# Sensor.net
KiCad netlist of a schematic drawn in Altium Designer
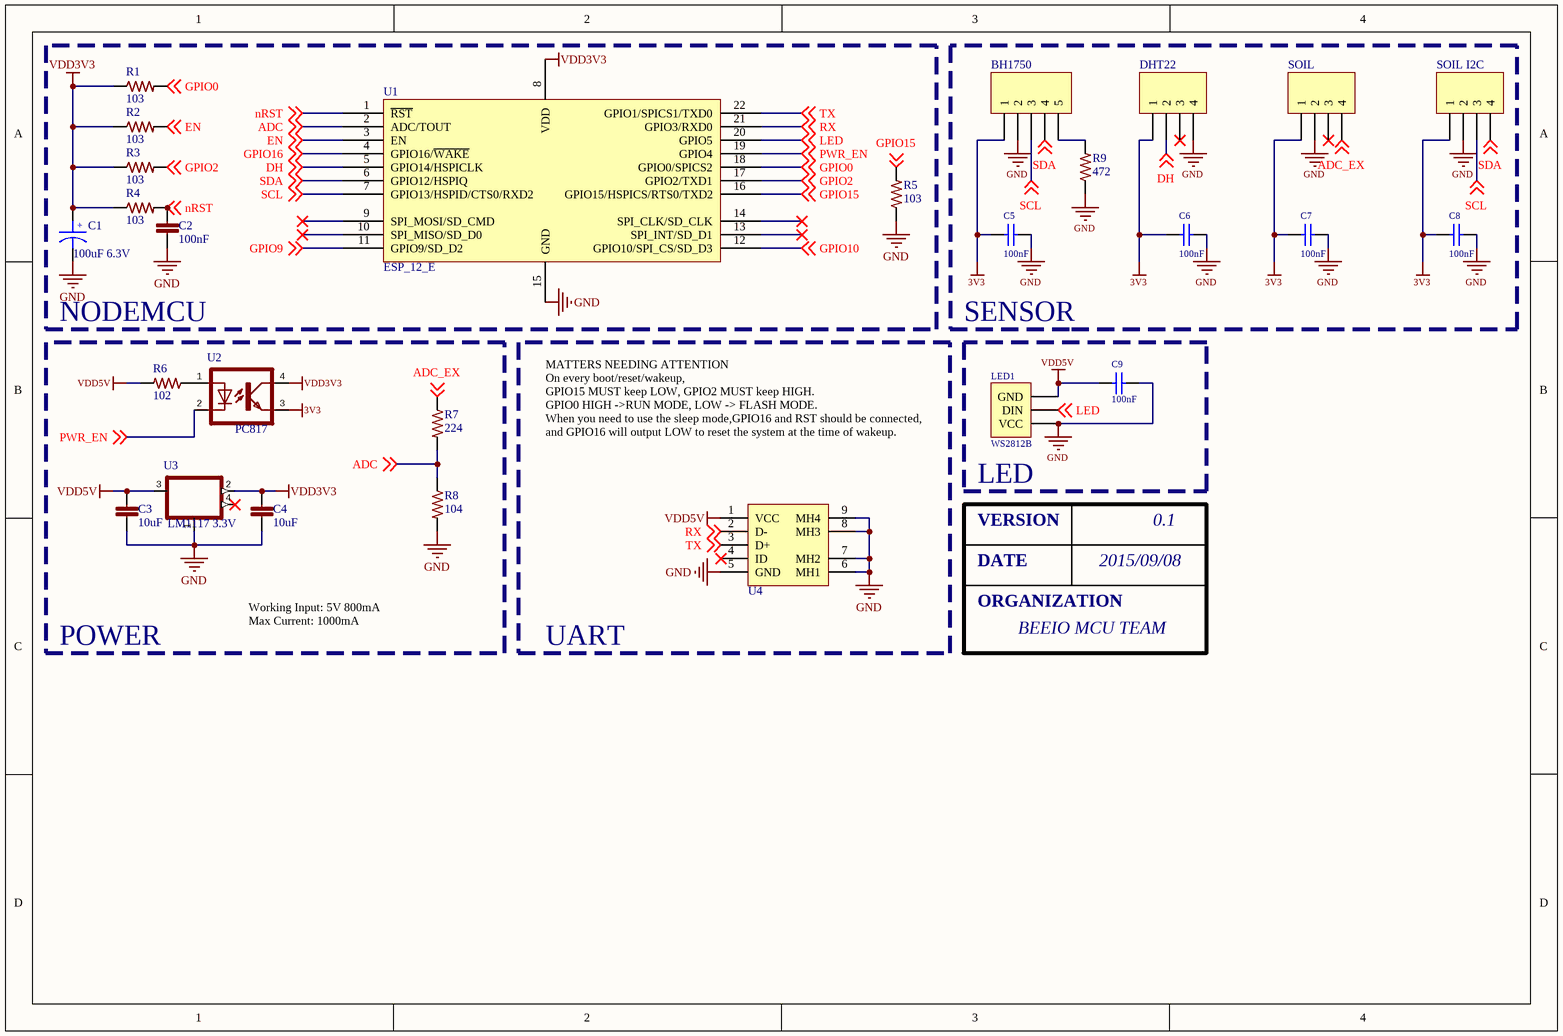
[diagram p0: Sensor.SchDoc]

(export (version "E")
  (design (tool "Eeschema 10.0.6"))
  (components
    (comp (ref "BH1750")
      (value "BH1750")
      (footprint "HDR1X5")
      (description "Header, 5-Pin")
      (fields (field (name "PUBLISHER") "Altium Limited"))
      (libsource (lib "Miscellaneous Connectors") (part "Header 5"))
    )
    (comp (ref "C1")
      (value "100uF 6.3V")
      (footprint "SMT_C_Tantalum_B")
      (description "Capacitor, SM Tantalum; Body 3.5 x 2.8 mm (LxW typ)")
      (libsource (lib "NODEMCU_DEVKIT_V1.0") (part "SMT_C_Tantalum_B"))
    )
    (comp (ref "C2") (value "100nF") (footprint "0603") (libsource (lib "") (part "CAP0603_1")))
    (comp (ref "C3") (value "10uF") (footprint "0603") (libsource (lib "SparkFun") (part "CAP0603")))
    (comp (ref "C4") (value "10uF") (footprint "0603") (libsource (lib "SparkFun") (part "CAP0603")))
    (comp (ref "C5")
      (value "100nF")
      (footprint "1608[0603]")
      (description "Capacitor (Semiconductor SIM Model)")
      (fields (field (name "PUBLISHER") "Altium Limited"))
      (libsource (lib "Miscellaneous Devices") (part "Cap Semi"))
    )
    (comp (ref "C6")
      (value "100nF")
      (footprint "1608[0603]")
      (description "Capacitor (Semiconductor SIM Model)")
      (fields (field (name "PUBLISHER") "Altium Limited"))
      (libsource (lib "Miscellaneous Devices") (part "Cap Semi"))
    )
    (comp (ref "C7")
      (value "100nF")
      (footprint "1608[0603]")
      (description "Capacitor (Semiconductor SIM Model)")
      (fields (field (name "PUBLISHER") "Altium Limited"))
      (libsource (lib "Miscellaneous Devices") (part "Cap Semi"))
    )
    (comp (ref "C8")
      (value "100nF")
      (footprint "1608[0603]")
      (description "Capacitor (Semiconductor SIM Model)")
      (fields (field (name "PUBLISHER") "Altium Limited"))
      (libsource (lib "Miscellaneous Devices") (part "Cap Semi"))
    )
    (comp (ref "C9")
      (value "100nF")
      (footprint "1608[0603]")
      (description "Capacitor (Semiconductor SIM Model)")
      (fields (field (name "PUBLISHER") "Altium Limited"))
      (libsource (lib "Miscellaneous Devices") (part "Cap Semi"))
    )
    (comp (ref "DHT22")
      (value "~")
      (footprint "HDR1X4")
      (description "Header, 4-Pin")
      (fields (field (name "PUBLISHER") "Altium Limited"))
      (libsource (lib "Miscellaneous Connectors") (part "Header 4"))
    )
    (comp (ref "LED1")
      (value "WS2812B")
      (footprint "HDR1X3")
      (description "Header, 3-Pin")
      (fields (field (name "PUBLISHER") "Altium Limited"))
      (libsource (lib "Miscellaneous Connectors") (part "Header 3"))
    )
    (comp (ref "R1") (value "103") (footprint "0603") (libsource (lib "SparkFun") (part "RESISTOR0603")))
    (comp (ref "R2") (value "103") (footprint "0603") (libsource (lib "SparkFun") (part "RESISTOR0603")))
    (comp (ref "R3") (value "103") (footprint "0603") (libsource (lib "SparkFun") (part "RESISTOR0603")))
    (comp (ref "R4") (value "103") (footprint "0603") (libsource (lib "SparkFun") (part "RESISTOR0603")))
    (comp (ref "R5") (value "103") (footprint "0603") (libsource (lib "SparkFun") (part "RESISTOR0603")))
    (comp (ref "R6") (value "102") (footprint "0603") (libsource (lib "SparkFun") (part "RESISTOR0603")))
    (comp (ref "R7") (value "224") (footprint "0603") (libsource (lib "SparkFun") (part "RESISTOR0603")))
    (comp (ref "R8") (value "104") (footprint "0603") (libsource (lib "SparkFun") (part "RESISTOR0603")))
    (comp (ref "R9") (value "472") (footprint "0603") (libsource (lib "SparkFun") (part "RESISTOR0603")))
    (comp (ref "SOIL")
      (value "~")
      (footprint "HDR1X4")
      (description "Header, 4-Pin")
      (fields (field (name "PUBLISHER") "Altium Limited"))
      (libsource (lib "Miscellaneous Connectors") (part "Header 4"))
    )
    (comp (ref "SOIL I2C")
      (value "BH1750")
      (footprint "HDR1X4")
      (description "Header, 4-Pin")
      (fields (field (name "PUBLISHER") "Altium Limited"))
      (libsource (lib "Miscellaneous Connectors") (part "Header 4"))
    )
    (comp (ref "U1")
      (value "ESP_12_E")
      (footprint "ESP_12_E_L")
      (description "ESP-12 Wi-Fi Module by AI-Thinker")
      (libsource (lib "NODEMCU_DEVKIT_V1.0") (part "ESP_12_E"))
    )
    (comp (ref "U2")
      (value "PC817")
      (footprint "DIL4-SMD")
      (fields (field (name "MPN") "PC817X4J000F"))
      (libsource (lib "optocoupler") (part "PC817"))
    )
    (comp (ref "U3")
      (value "LM1117 3.3V")
      (footprint "SOT223")
      (libsource (lib "SparkFun-PowerIC") (part "V_REG_LM1117SOT223"))
    )
    (comp (ref "U4")
      (value "Micro USB 5S DIP")
      (footprint "USB_MICRO_5S_B")
      (description "USB micro female SMT with 4 fixed foot")
      (libsource (lib "NODEMCU_DEVKIT_V1.0") (part "USB_Micro_5S_B"))
    )
  )
  (nets
    (net (code "1") (name "3V3") (class "Default")
      (node (ref "BH1750") (pin "1") (pinfunction "1_1") (pintype "passive"))
      (node (ref "C5") (pin "1") (pinfunction "1_1") (pintype "passive"))
      (node (ref "C6") (pin "1") (pinfunction "1_1") (pintype "passive"))
      (node (ref "C7") (pin "1") (pinfunction "1_1") (pintype "passive"))
      (node (ref "C8") (pin "1") (pinfunction "1_1") (pintype "passive"))
      (node (ref "DHT22") (pin "1") (pinfunction "1_1") (pintype "passive"))
      (node (ref "SOIL") (pin "1") (pinfunction "1_1") (pintype "passive"))
      (node (ref "SOIL I2C") (pin "1") (pinfunction "1_1") (pintype "passive"))
      (node (ref "U2") (pin "3") (pinfunction "EMIT_3") (pintype "passive"))
    )
    (net (code "2") (name "ADC") (class "Default")
      (node (ref "R7") (pin "2") (pinfunction "2_2") (pintype "passive"))
      (node (ref "R8") (pin "1") (pinfunction "1_1") (pintype "passive"))
      (node (ref "U1") (pin "2") (pinfunction "ADC/TOUT_2") (pintype "passive"))
    )
    (net (code "3") (name "ADC_EX") (class "Default")
      (node (ref "R7") (pin "1") (pinfunction "1_1") (pintype "passive"))
      (node (ref "SOIL") (pin "4") (pinfunction "4_4") (pintype "passive"))
    )
    (net (code "4") (name "DH") (class "Default")
      (node (ref "DHT22") (pin "2") (pinfunction "2_2") (pintype "passive"))
      (node (ref "U1") (pin "5") (pinfunction "GPIO14/HSPICLK_5") (pintype "passive"))
    )
    (net (code "5") (name "EN") (class "Default")
      (node (ref "R2") (pin "2") (pinfunction "2_2") (pintype "passive"))
      (node (ref "U1") (pin "3") (pinfunction "EN_3") (pintype "passive"))
    )
    (net (code "6") (name "GND") (class "Default")
      (node (ref "BH1750") (pin "2") (pinfunction "2_2") (pintype "passive"))
      (node (ref "C1") (pin "2") (pinfunction "2_2") (pintype "passive"))
      (node (ref "C2") (pin "2") (pinfunction "2_2") (pintype "passive"))
      (node (ref "C3") (pin "1") (pinfunction "1_1") (pintype "passive"))
      (node (ref "C4") (pin "1") (pinfunction "1_1") (pintype "passive"))
      (node (ref "C5") (pin "2") (pinfunction "2_2") (pintype "passive"))
      (node (ref "C6") (pin "2") (pinfunction "2_2") (pintype "passive"))
      (node (ref "C7") (pin "2") (pinfunction "2_2") (pintype "passive"))
      (node (ref "C8") (pin "2") (pinfunction "2_2") (pintype "passive"))
      (node (ref "C9") (pin "2") (pinfunction "2_2") (pintype "passive"))
      (node (ref "DHT22") (pin "4") (pinfunction "4_4") (pintype "passive"))
      (node (ref "LED1") (pin "1") (pinfunction "VCC_1") (pintype "passive"))
      (node (ref "R5") (pin "1") (pinfunction "1_1") (pintype "passive"))
      (node (ref "R8") (pin "2") (pinfunction "2_2") (pintype "passive"))
      (node (ref "R9") (pin "1") (pinfunction "1_1") (pintype "passive"))
      (node (ref "SOIL") (pin "2") (pinfunction "2_2") (pintype "passive"))
      (node (ref "SOIL I2C") (pin "2") (pinfunction "2_2") (pintype "passive"))
      (node (ref "U1") (pin "15") (pinfunction "GND_15") (pintype "passive"))
      (node (ref "U3") (pin "1") (pinfunction "ADJ_1") (pintype "passive"))
      (node (ref "U4") (pin "5") (pinfunction "GND_5") (pintype "passive"))
      (node (ref "U4") (pin "6") (pinfunction "MH1_6") (pintype "passive"))
      (node (ref "U4") (pin "7") (pinfunction "MH2_7") (pintype "passive"))
      (node (ref "U4") (pin "8") (pinfunction "MH3_8") (pintype "passive"))
      (node (ref "U4") (pin "9") (pinfunction "MH4_9") (pintype "passive"))
    )
    (net (code "7") (name "GPIO0") (class "Default")
      (node (ref "R1") (pin "2") (pinfunction "2_2") (pintype "passive"))
      (node (ref "U1") (pin "18") (pinfunction "GPIO0/SPICS2_18") (pintype "passive"))
    )
    (net (code "8") (name "GPIO2") (class "Default")
      (node (ref "R3") (pin "2") (pinfunction "2_2") (pintype "passive"))
      (node (ref "U1") (pin "17") (pinfunction "GPIO2/TXD1_17") (pintype "passive"))
    )
    (net (code "9") (name "GPIO9") (class "Default")
      (node (ref "U1") (pin "11") (pinfunction "GPIO9/SD_D2_11") (pintype "passive"))
    )
    (net (code "10") (name "GPIO10") (class "Default")
      (node (ref "U1") (pin "12") (pinfunction "GPIO10/SPI_CS/SD_D3_12") (pintype "passive"))
    )
    (net (code "11") (name "GPIO15") (class "Default")
      (node (ref "R5") (pin "2") (pinfunction "2_2") (pintype "passive"))
      (node (ref "U1") (pin "16") (pinfunction "GPIO15/HSPICS/RTS0/TXD2_16") (pintype "passive"))
    )
    (net (code "12") (name "GPIO16") (class "Default")
      (node (ref "U1") (pin "4") (pinfunction "GPIO16/~{WAKE}_4") (pintype "passive"))
    )
    (net (code "13") (name "LED") (class "Default")
      (node (ref "LED1") (pin "2") (pinfunction "DIN_2") (pintype "passive"))
      (node (ref "U1") (pin "20") (pinfunction "GPIO5_20") (pintype "passive"))
    )
    (net (code "14") (name "Net-(BH1750-Pad5)") (class "Default")
      (node (ref "BH1750") (pin "5") (pinfunction "5_5") (pintype "passive"))
      (node (ref "R9") (pin "2") (pinfunction "2_2") (pintype "passive"))
    )
    (net (code "15") (name "Net-(U2-A)") (class "Default")
      (node (ref "R6") (pin "1") (pinfunction "1_1") (pintype "passive"))
      (node (ref "U2") (pin "1") (pinfunction "A_1") (pintype "passive"))
    )
    (net (code "16") (name "PWR_EN") (class "Default")
      (node (ref "U1") (pin "19") (pinfunction "GPIO4_19") (pintype "passive"))
      (node (ref "U2") (pin "2") (pinfunction "C_2") (pintype "passive"))
    )
    (net (code "17") (name "RX") (class "Default")
      (node (ref "U1") (pin "21") (pinfunction "GPIO3/RXD0_21") (pintype "passive"))
      (node (ref "U4") (pin "2") (pinfunction "D-_2") (pintype "passive"))
    )
    (net (code "18") (name "SCL") (class "Default")
      (node (ref "BH1750") (pin "3") (pinfunction "3_3") (pintype "passive"))
      (node (ref "SOIL I2C") (pin "3") (pinfunction "3_3") (pintype "passive"))
      (node (ref "U1") (pin "7") (pinfunction "GPIO13/HSPID/CTS0/RXD2_7") (pintype "passive"))
    )
    (net (code "19") (name "SDA") (class "Default")
      (node (ref "BH1750") (pin "4") (pinfunction "4_4") (pintype "passive"))
      (node (ref "SOIL I2C") (pin "4") (pinfunction "4_4") (pintype "passive"))
      (node (ref "U1") (pin "6") (pinfunction "GPIO12/HSPIQ_6") (pintype "passive"))
    )
    (net (code "20") (name "TX") (class "Default")
      (node (ref "U1") (pin "22") (pinfunction "GPIO1/SPICS1/TXD0_22") (pintype "passive"))
      (node (ref "U4") (pin "3") (pinfunction "D+_3") (pintype "passive"))
    )
    (net (code "21") (name "VDD3V3") (class "Default")
      (node (ref "C1") (pin "1") (pinfunction "1_1") (pintype "passive"))
      (node (ref "C4") (pin "2") (pinfunction "2_2") (pintype "passive"))
      (node (ref "R1") (pin "1") (pinfunction "1_1") (pintype "passive"))
      (node (ref "R2") (pin "1") (pinfunction "1_1") (pintype "passive"))
      (node (ref "R3") (pin "1") (pinfunction "1_1") (pintype "passive"))
      (node (ref "R4") (pin "1") (pinfunction "1_1") (pintype "passive"))
      (node (ref "U1") (pin "8") (pinfunction "VDD_8") (pintype "passive"))
      (node (ref "U2") (pin "4") (pinfunction "COL_4") (pintype "passive"))
      (node (ref "U3") (pin "2") (pinfunction "OUT_2") (pintype "output"))
    )
    (net (code "22") (name "VDD5V") (class "Default")
      (node (ref "C3") (pin "2") (pinfunction "2_2") (pintype "passive"))
      (node (ref "C9") (pin "1") (pinfunction "1_1") (pintype "passive"))
      (node (ref "LED1") (pin "3") (pinfunction "GND_3") (pintype "passive"))
      (node (ref "R6") (pin "2") (pinfunction "2_2") (pintype "passive"))
      (node (ref "U3") (pin "3") (pinfunction "IN_3") (pintype "passive"))
      (node (ref "U4") (pin "1") (pinfunction "VCC_1") (pintype "passive"))
    )
    (net (code "23") (name "nRST") (class "Default")
      (node (ref "C2") (pin "1") (pinfunction "1_1") (pintype "passive"))
      (node (ref "R4") (pin "2") (pinfunction "2_2") (pintype "passive"))
      (node (ref "U1") (pin "1") (pinfunction "~{RST}_1") (pintype "passive"))
    )
    (net (code "24") (name "unconnected-(DHT22-Pad3)") (class "Default")
      (node (ref "DHT22") (pin "3") (pinfunction "3_3") (pintype "passive+no_connect"))
    )
    (net (code "25") (name "unconnected-(SOIL-Pad3)") (class "Default")
      (node (ref "SOIL") (pin "3") (pinfunction "3_3") (pintype "passive+no_connect"))
    )
    (net (code "26") (name "unconnected-(U1-SPI_CLK{slash}SD_CLK-Pad14)") (class "Default")
      (node (ref "U1") (pin "14") (pinfunction "SPI_CLK/SD_CLK_14") (pintype "passive+no_connect"))
    )
    (net (code "27") (name "unconnected-(U1-SPI_INT{slash}SD_D1-Pad13)") (class "Default")
      (node (ref "U1") (pin "13") (pinfunction "SPI_INT/SD_D1_13") (pintype "passive+no_connect"))
    )
    (net (code "28") (name "unconnected-(U1-SPI_MISO{slash}SD_D0-Pad10)") (class "Default")
      (node (ref "U1") (pin "10") (pinfunction "SPI_MISO/SD_D0_10") (pintype "passive+no_connect"))
    )
    (net (code "29") (name "unconnected-(U1-SPI_MOSI{slash}SD_CMD-Pad9)") (class "Default")
      (node (ref "U1") (pin "9") (pinfunction "SPI_MOSI/SD_CMD_9") (pintype "passive+no_connect"))
    )
    (net (code "30") (name "unconnected-(U3-OUT-Pad4)") (class "Default")
      (node (ref "U3") (pin "4") (pinfunction "OUT_4") (pintype "output+no_connect"))
    )
    (net (code "31") (name "unconnected-(U4-ID-Pad4)") (class "Default")
      (node (ref "U4") (pin "4") (pinfunction "ID_4") (pintype "passive+no_connect"))
    )
  )
)
